# MCU.net
KiCad netlist of a schematic drawn in Altium Designer
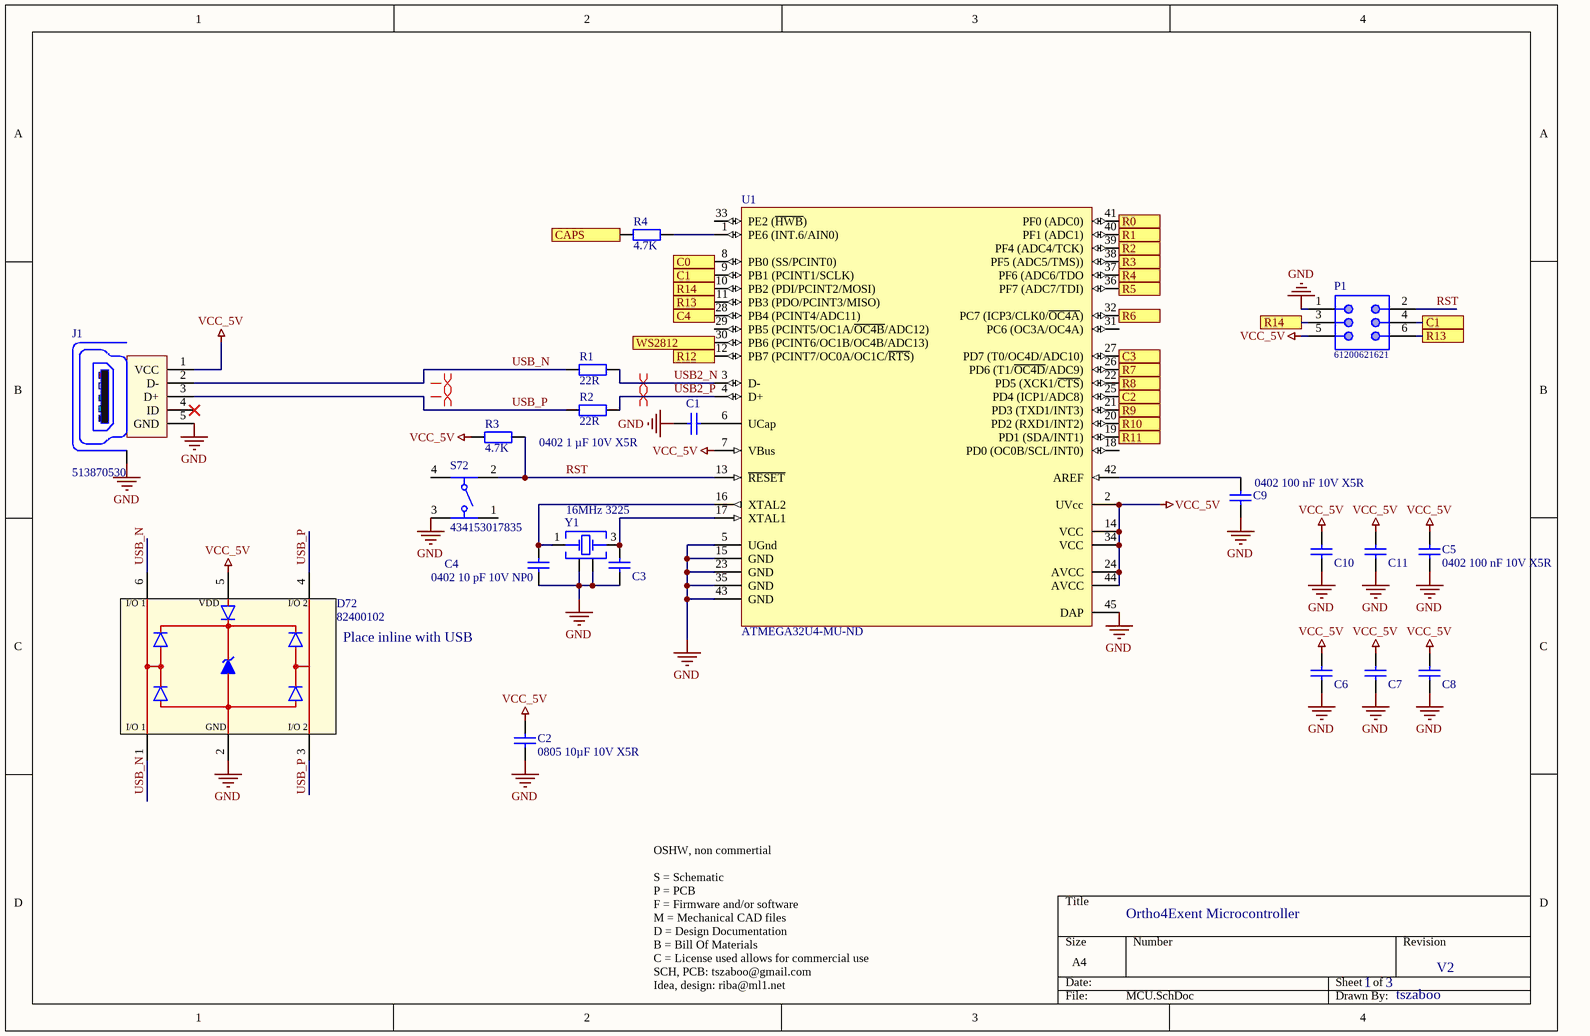
[diagram p0: MCU.SchDoc]

(export (version "E")
  (design (tool "Eeschema 10.0.6"))
  (components
    (comp (ref "C1")
      (value "0402 1µF")
      (footprint "CAPC0402N")
      (fields (field (name "SCH") "0402 1 µF 10V X5R") (field (name "VOLTAGE") "10"))
      (libsource (lib "WCAP") (part "Cap"))
    )
    (comp (ref "C2")
      (value "0805 10µF")
      (footprint "CAPC0805N")
      (fields (field (name "SCH") "0805 10µF 10V X5R") (field (name "VOLTAGE") "10"))
      (libsource (lib "WCAP") (part "Cap"))
    )
    (comp (ref "C3")
      (value "0402 10pF")
      (footprint "CAPC0402N")
      (fields (field (name "VOLTAGE") "10"))
      (libsource (lib "WCAP") (part "Cap"))
    )
    (comp (ref "C4")
      (value "0402 10pF")
      (footprint "CAPC0402N")
      (fields (field (name "SCH") "0402 10 pF 10V NP0") (field (name "VOLTAGE") "10"))
      (libsource (lib "WCAP") (part "Cap"))
    )
    (comp (ref "C5")
      (value "0402 100nF")
      (footprint "CAPC0402N")
      (fields (field (name "SCH") "0402 100 nF 10V X5R") (field (name "VOLTAGE") "10"))
      (libsource (lib "WCAP") (part "Cap"))
    )
    (comp (ref "C6")
      (value "0402 100nF")
      (footprint "CAPC0402N")
      (fields (field (name "VOLTAGE") "10"))
      (libsource (lib "WCAP") (part "Cap"))
    )
    (comp (ref "C7")
      (value "0402 100nF")
      (footprint "CAPC0402N")
      (fields (field (name "VOLTAGE") "10"))
      (libsource (lib "WCAP") (part "Cap"))
    )
    (comp (ref "C8")
      (value "0402 100nF")
      (footprint "CAPC0402N")
      (fields (field (name "VOLTAGE") "10"))
      (libsource (lib "WCAP") (part "Cap"))
    )
    (comp (ref "C9")
      (value "0402 100nF")
      (footprint "CAPC0402N")
      (fields (field (name "SCH") "0402 100 nF 10V X5R") (field (name "VOLTAGE") "10"))
      (libsource (lib "WCAP") (part "Cap"))
    )
    (comp (ref "C10")
      (value "0402 100nF")
      (footprint "CAPC0402N")
      (fields (field (name "VOLTAGE") "10"))
      (libsource (lib "WCAP") (part "Cap"))
    )
    (comp (ref "C11")
      (value "0402 100nF")
      (footprint "CAPC0402N")
      (fields (field (name "VOLTAGE") "10"))
      (libsource (lib "WCAP") (part "Cap"))
    )
    (comp (ref "D72")
      (value "82400102")
      (footprint "SOT23-6L")
      (description "WE-TVS TVS Diode, High Speed Series, SOT23-6L, VDC = 5V")
      (libsource (lib "WE-TVS_rev16a") (part "WE-TVS, SOT23-6L, 82400102"))
    )
    (comp (ref "J1")
      (value "513870530")
      (footprint "513870530:513870530")
      (libsource (lib "513870530") (part "513870530"))
    )
    (comp (ref "P1")
      (value "61200621621")
      (footprint "61200621621")
      (description "Male Box Header WR-BHD, THT, Vertical, pitch 2.54 mm, 6 pins")
      (libsource (lib "Altium_WR-BHD (rev19a)") (part "61200621621"))
    )
    (comp (ref "R1")
      (value "22R")
      (footprint "RESC0603N")
      (description "Resistor")
      (fields (field (name "Comment") "RES 22R 0603"))
      (libsource (lib "VISHAY CRCW") (part "Res"))
    )
    (comp (ref "R2")
      (value "22R")
      (footprint "RESC0603N")
      (description "Resistor")
      (fields (field (name "Comment") "RES 22R 0603"))
      (libsource (lib "VISHAY CRCW") (part "Res"))
    )
    (comp (ref "R3")
      (value "4.7K")
      (footprint "RESC0402N")
      (description "Resistor")
      (fields (field (name "Comment") "RES 4.7K 0402"))
      (libsource (lib "") (part "Res_1"))
    )
    (comp (ref "R4")
      (value "4.7K")
      (footprint "RESC0402N")
      (description "Resistor")
      (fields (field (name "Comment") "RES 4.7K 0402"))
      (libsource (lib "") (part "Res_1"))
    )
    (comp (ref "S72")
      (value "434153017835")
      (footprint "434153017835")
      (description "WS-TASV J-Bend SMT Tact Switch, 3.5x2.9x1.7mm, 350gf")
      (libsource (lib "Altium_WS-TASV (rev20b)") (part "434153017835"))
    )
    (comp (ref "U1")
      (value "ATMEGA32U4-MU-ND")
      (footprint "44PW_M")
      (libsource (lib "Altium Content Vault") (part "MC-8B-ATM16U4-SQ45"))
    )
    (comp (ref "Y1")
      (value "16MHz 3225")
      (footprint "WE-XTAL_CFPX-180")
      (description "WE-XTAL Quartz Crystal, SMT, CFPX-180, 16MHz, +/-20ppm")
      (libsource (lib "Altium_WE-XTAL (rev20c)") (part "830055951"))
    )
  )
  (nets
    (net (code "1") (name "/C0") (class "Default")
      (node (ref "U1") (pin "8") (pinfunction "PB0_(SS/PCINT0)_8") (pintype "bidirectional"))
    )
    (net (code "2") (name "/C1") (class "Default")
      (node (ref "P1") (pin "4") (pinfunction "4_4") (pintype "passive"))
      (node (ref "U1") (pin "9") (pinfunction "PB1_(PCINT1/SCLK)_9") (pintype "bidirectional"))
    )
    (net (code "3") (name "/C2") (class "Default")
      (node (ref "U1") (pin "25") (pinfunction "PD4_(ICP1/ADC8)_25") (pintype "bidirectional"))
    )
    (net (code "4") (name "/C3") (class "Default")
      (node (ref "U1") (pin "27") (pinfunction "PD7_(T0/OC4D/ADC10)_27") (pintype "bidirectional"))
    )
    (net (code "5") (name "/C4") (class "Default")
      (node (ref "U1") (pin "28") (pinfunction "PB4_(PCINT4/ADC11)_28") (pintype "bidirectional"))
    )
    (net (code "6") (name "/CAPS") (class "Default")
      (node (ref "R4") (pin "2") (pinfunction "2_2") (pintype "passive"))
    )
    (net (code "7") (name "/R0") (class "Default")
      (node (ref "U1") (pin "41") (pinfunction "PF0_(ADC0)_41") (pintype "bidirectional"))
    )
    (net (code "8") (name "/R1") (class "Default")
      (node (ref "U1") (pin "40") (pinfunction "PF1_(ADC1)_40") (pintype "bidirectional"))
    )
    (net (code "9") (name "/R2") (class "Default")
      (node (ref "U1") (pin "39") (pinfunction "PF4_(ADC4/TCK)_39") (pintype "bidirectional"))
    )
    (net (code "10") (name "/R3") (class "Default")
      (node (ref "U1") (pin "38") (pinfunction "PF5_(ADC5/TMS))_38") (pintype "bidirectional"))
    )
    (net (code "11") (name "/R4") (class "Default")
      (node (ref "U1") (pin "37") (pinfunction "PF6_(ADC6/TDO_37") (pintype "bidirectional"))
    )
    (net (code "12") (name "/R5") (class "Default")
      (node (ref "U1") (pin "36") (pinfunction "PF7_(ADC7/TDI)_36") (pintype "bidirectional"))
    )
    (net (code "13") (name "/R6") (class "Default")
      (node (ref "U1") (pin "32") (pinfunction "PC7_(ICP3/CLK0/~{OC4A})_32") (pintype "bidirectional"))
    )
    (net (code "14") (name "/R7") (class "Default")
      (node (ref "U1") (pin "26") (pinfunction "PD6_(T1/~{OC4D}/ADC9)_26") (pintype "bidirectional"))
    )
    (net (code "15") (name "/R8") (class "Default")
      (node (ref "U1") (pin "22") (pinfunction "PD5_(XCK1/~{CTS})_22") (pintype "bidirectional"))
    )
    (net (code "16") (name "/R9") (class "Default")
      (node (ref "U1") (pin "21") (pinfunction "PD3_(TXD1/INT3)_21") (pintype "bidirectional"))
    )
    (net (code "17") (name "/R10") (class "Default")
      (node (ref "U1") (pin "20") (pinfunction "PD2_(RXD1/INT2)_20") (pintype "bidirectional"))
    )
    (net (code "18") (name "/R11") (class "Default")
      (node (ref "U1") (pin "19") (pinfunction "PD1_(SDA/INT1)_19") (pintype "bidirectional"))
    )
    (net (code "19") (name "/R12") (class "Default")
      (node (ref "U1") (pin "12") (pinfunction "PB7_(PCINT7/OC0A/OC1C/~{RTS})_12") (pintype "bidirectional"))
    )
    (net (code "20") (name "/R13") (class "Default")
      (node (ref "P1") (pin "6") (pinfunction "6_6") (pintype "passive"))
      (node (ref "U1") (pin "11") (pinfunction "PB3_(PDO/PCINT3/MISO)_11") (pintype "bidirectional"))
    )
    (net (code "21") (name "/R14") (class "Default")
      (node (ref "P1") (pin "3") (pinfunction "3_3") (pintype "passive"))
      (node (ref "U1") (pin "10") (pinfunction "PB2_(PDI/PCINT2/MOSI)_10") (pintype "bidirectional"))
    )
    (net (code "22") (name "/RST") (class "Default")
      (node (ref "P1") (pin "2") (pinfunction "2_2") (pintype "passive"))
      (node (ref "R3") (pin "1") (pinfunction "1_1") (pintype "passive"))
      (node (ref "S72") (pin "2") (pinfunction "2_2") (pintype "passive"))
      (node (ref "U1") (pin "13") (pinfunction "~{RESET}_13") (pintype "input"))
    )
    (net (code "23") (name "/USB2_N") (class "Default")
      (node (ref "R1") (pin "2") (pinfunction "2_2") (pintype "passive"))
      (node (ref "U1") (pin "3") (pinfunction "D-_3") (pintype "bidirectional"))
    )
    (net (code "24") (name "/USB2_P") (class "Default")
      (node (ref "R2") (pin "2") (pinfunction "2_2") (pintype "passive"))
      (node (ref "U1") (pin "4") (pinfunction "D+_4") (pintype "bidirectional"))
    )
    (net (code "25") (name "/USB_N") (class "Default")
      (node (ref "D72") (pin "1") (pinfunction "I/O_1_1") (pintype "passive"))
      (node (ref "D72") (pin "6") (pinfunction "I/O_1_6") (pintype "passive"))
      (node (ref "J1") (pin "2") (pinfunction "D-_2") (pintype "passive"))
      (node (ref "R1") (pin "1") (pinfunction "1_1") (pintype "passive"))
    )
    (net (code "26") (name "/USB_P") (class "Default")
      (node (ref "D72") (pin "3") (pinfunction "I/O_2_3") (pintype "passive"))
      (node (ref "D72") (pin "4") (pinfunction "I/O_2_4") (pintype "passive"))
      (node (ref "J1") (pin "3") (pinfunction "D+_3") (pintype "passive"))
      (node (ref "R2") (pin "1") (pinfunction "1_1") (pintype "passive"))
    )
    (net (code "27") (name "/WS2812") (class "Default")
      (node (ref "U1") (pin "30") (pinfunction "PB6_(PCINT6/OC1B/OC4B/ADC13)_30") (pintype "bidirectional"))
    )
    (net (code "28") (name "GND") (class "Default")
      (node (ref "C1") (pin "1") (pinfunction "1_1") (pintype "passive"))
      (node (ref "C10") (pin "1") (pinfunction "1_1") (pintype "passive"))
      (node (ref "C11") (pin "1") (pinfunction "1_1") (pintype "passive"))
      (node (ref "C2") (pin "1") (pinfunction "1_1") (pintype "passive"))
      (node (ref "C3") (pin "1") (pinfunction "1_1") (pintype "passive"))
      (node (ref "C4") (pin "1") (pinfunction "1_1") (pintype "passive"))
      (node (ref "C5") (pin "1") (pinfunction "1_1") (pintype "passive"))
      (node (ref "C6") (pin "1") (pinfunction "1_1") (pintype "passive"))
      (node (ref "C7") (pin "1") (pinfunction "1_1") (pintype "passive"))
      (node (ref "C8") (pin "1") (pinfunction "1_1") (pintype "passive"))
      (node (ref "C9") (pin "1") (pinfunction "1_1") (pintype "passive"))
      (node (ref "D72") (pin "2") (pinfunction "GND_2") (pintype "passive"))
      (node (ref "J1") (pin "5") (pinfunction "GND_5") (pintype "passive"))
      (node (ref "J1") (pin "TAB") (pinfunction "TAB_TAB") (pintype "passive"))
      (node (ref "P1") (pin "1") (pinfunction "1_1") (pintype "passive"))
      (node (ref "S72") (pin "3") (pinfunction "3_3") (pintype "passive"))
      (node (ref "U1") (pin "15") (pinfunction "GND_15") (pintype "power_in"))
      (node (ref "U1") (pin "23") (pinfunction "GND_23") (pintype "power_in"))
      (node (ref "U1") (pin "35") (pinfunction "GND_35") (pintype "power_in"))
      (node (ref "U1") (pin "43") (pinfunction "GND_43") (pintype "power_in"))
      (node (ref "U1") (pin "45") (pinfunction "DAP_45") (pintype "power_in"))
      (node (ref "U1") (pin "5") (pinfunction "UGnd_5") (pintype "power_in"))
      (node (ref "Y1") (pin "2") (pinfunction "GND_2") (pintype "passive"))
      (node (ref "Y1") (pin "4") (pinfunction "GND_4") (pintype "passive"))
    )
    (net (code "29") (name "Net-(U1-AREF)") (class "Default")
      (node (ref "C9") (pin "2") (pinfunction "2_2") (pintype "passive"))
      (node (ref "U1") (pin "42") (pinfunction "AREF_42") (pintype "input"))
    )
    (net (code "30") (name "Net-(U1-PE6_(INT.6{slash}AIN0))") (class "Default")
      (node (ref "R4") (pin "1") (pinfunction "1_1") (pintype "passive"))
      (node (ref "U1") (pin "1") (pinfunction "PE6_(INT.6/AIN0)_1") (pintype "bidirectional"))
    )
    (net (code "31") (name "Net-(U1-UCap)") (class "Default")
      (node (ref "C1") (pin "2") (pinfunction "2_2") (pintype "passive"))
      (node (ref "U1") (pin "6") (pinfunction "UCap_6") (pintype "passive"))
    )
    (net (code "32") (name "Net-(U1-XTAL1)") (class "Default")
      (node (ref "C3") (pin "2") (pinfunction "2_2") (pintype "passive"))
      (node (ref "U1") (pin "17") (pinfunction "XTAL1_17") (pintype "input"))
      (node (ref "Y1") (pin "3") (pinfunction "Crystal_3") (pintype "passive"))
    )
    (net (code "33") (name "Net-(U1-XTAL2)") (class "Default")
      (node (ref "C4") (pin "2") (pinfunction "2_2") (pintype "passive"))
      (node (ref "U1") (pin "16") (pinfunction "XTAL2_16") (pintype "output"))
      (node (ref "Y1") (pin "1") (pinfunction "Crystal_1") (pintype "passive"))
    )
    (net (code "34") (name "VCC_5V") (class "Default")
      (node (ref "C10") (pin "2") (pinfunction "2_2") (pintype "passive"))
      (node (ref "C11") (pin "2") (pinfunction "2_2") (pintype "passive"))
      (node (ref "C2") (pin "2") (pinfunction "2_2") (pintype "passive"))
      (node (ref "C5") (pin "2") (pinfunction "2_2") (pintype "passive"))
      (node (ref "C6") (pin "2") (pinfunction "2_2") (pintype "passive"))
      (node (ref "C7") (pin "2") (pinfunction "2_2") (pintype "passive"))
      (node (ref "C8") (pin "2") (pinfunction "2_2") (pintype "passive"))
      (node (ref "D72") (pin "5") (pinfunction "VDD_5") (pintype "passive"))
      (node (ref "J1") (pin "1") (pinfunction "VCC_1") (pintype "passive"))
      (node (ref "P1") (pin "5") (pinfunction "5_5") (pintype "passive"))
      (node (ref "R3") (pin "2") (pinfunction "2_2") (pintype "passive"))
      (node (ref "U1") (pin "14") (pinfunction "VCC_14") (pintype "power_in"))
      (node (ref "U1") (pin "2") (pinfunction "UVcc_2") (pintype "power_in"))
      (node (ref "U1") (pin "24") (pinfunction "AVCC_24") (pintype "power_in"))
      (node (ref "U1") (pin "34") (pinfunction "VCC_34") (pintype "power_in"))
      (node (ref "U1") (pin "44") (pinfunction "AVCC_44") (pintype "power_in"))
      (node (ref "U1") (pin "7") (pinfunction "VBus_7") (pintype "input"))
    )
    (net (code "35") (name "unconnected-(J1-ID-Pad4)") (class "Default")
      (node (ref "J1") (pin "4") (pinfunction "ID_4") (pintype "passive+no_connect"))
    )
    (net (code "36") (name "unconnected-(S72-Pad1)") (class "Default")
      (node (ref "S72") (pin "1") (pinfunction "1_1") (pintype "passive"))
    )
    (net (code "37") (name "unconnected-(S72-Pad4)") (class "Default")
      (node (ref "S72") (pin "4") (pinfunction "4_4") (pintype "passive"))
    )
    (net (code "38") (name "unconnected-(U1-PB5_(PCINT5{slash}OC1A{slash}~{OC4B}{slash}ADC12)-Pad29)") (class "Default")
      (node (ref "U1") (pin "29") (pinfunction "PB5_(PCINT5/OC1A/~{OC4B}/ADC12)_29") (pintype "bidirectional"))
    )
    (net (code "39") (name "unconnected-(U1-PC6_(OC3A{slash}OC4A)-Pad31)") (class "Default")
      (node (ref "U1") (pin "31") (pinfunction "PC6_(OC3A/OC4A)_31") (pintype "bidirectional"))
    )
    (net (code "40") (name "unconnected-(U1-PD0_(OC0B{slash}SCL{slash}INT0)-Pad18)") (class "Default")
      (node (ref "U1") (pin "18") (pinfunction "PD0_(OC0B/SCL/INT0)_18") (pintype "bidirectional"))
    )
    (net (code "41") (name "unconnected-(U1-PE2_(~{HWB})-Pad33)") (class "Default")
      (node (ref "U1") (pin "33") (pinfunction "PE2_(~{HWB})_33") (pintype "bidirectional"))
    )
  )
)
